# MCU_and_Power_Mgmt.net
KiCad netlist of a schematic drawn in Altium Designer
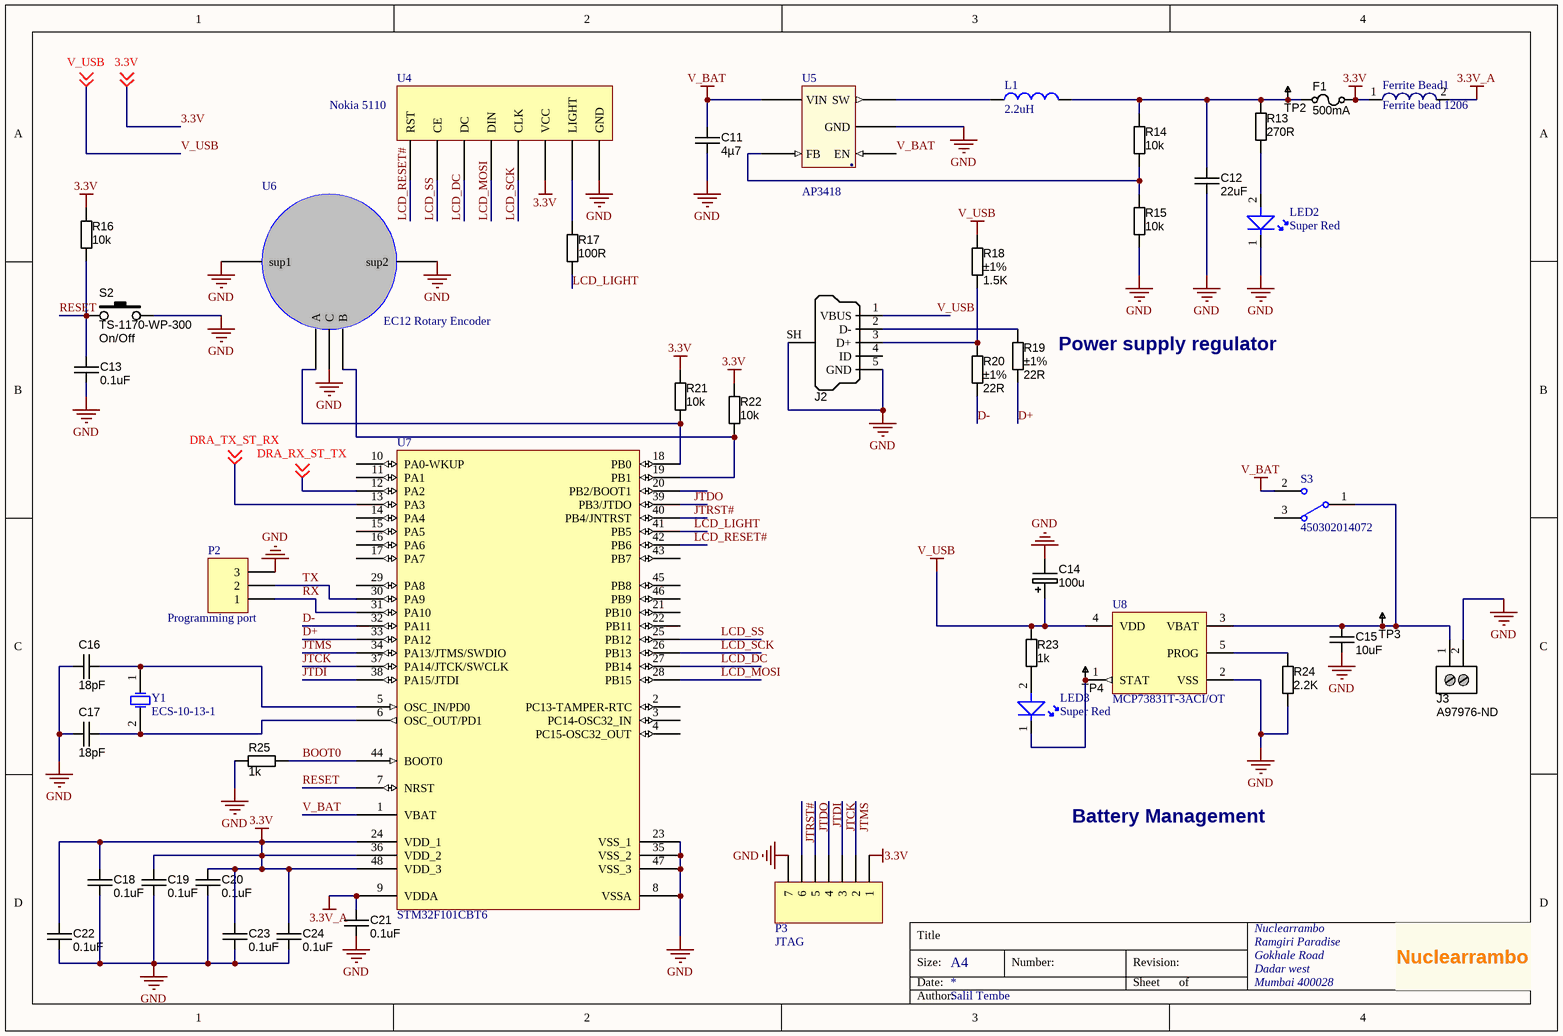
[diagram p0: MCU_and_Power_Mgmt.SchDoc]

(export (version "E")
  (design (tool "Eeschema 10.0.6"))
  (components
    (comp (ref "C11")
      (value "4µ7")
      (footprint "CAPMP3216X180N")
      (description "Capacitor SMD Cer 4.7uF 10% 16V X5R 0805")
      (fields (field (name "TOLERANCE") "±10%"))
      (libsource (lib "PBL - Capacitors") (part "CAPC_4u7_0805"))
    )
    (comp (ref "C12")
      (value "22uF")
      (footprint "CAPMP3216X180N")
      (description "Capacitor SMD Cer 4.7uF 10% 16V X5R 0805")
      (fields (field (name "TOLERANCE") "±10%"))
      (libsource (lib "PBL - Capacitors") (part "CAPC_4u7_0805"))
    )
    (comp (ref "C13")
      (value "0.1uF")
      (footprint "CAPC2012X135N")
      (description "Capacitor SMD Cer 10uF 10% 10V X5R 0805")
      (fields (field (name "TOLERANCE") "±10%"))
      (libsource (lib "PBL - Capacitors") (part "CAPC_10u_0805_10V"))
    )
    (comp (ref "C14")
      (value "100u")
      (footprint "CAPMP7343X310N")
      (description "Capacitor SMD Tant 330uF 20% 6V3 2917")
      (fields
        (field (name "TOLERANCE") "±20%")
        (field (name "MANUFACTURER PART NUMBER") "T520D337M006ATE015")
      )
      (libsource (lib "PBL - Capacitors") (part "CAPT_330u_2917_6V3"))
    )
    (comp (ref "C15")
      (value "10uF")
      (footprint "CAPMP3216X180N")
      (description "Capacitor SMD Cer 4.7uF 10% 16V X5R 0805")
      (fields (field (name "TOLERANCE") "±10%"))
      (libsource (lib "PBL - Capacitors") (part "CAPC_4u7_0805"))
    )
    (comp (ref "C16")
      (value "18pF")
      (footprint "CAPC2012X135N")
      (description "Capacitor SMD Cer 10uF 10% 10V X5R 0805")
      (fields (field (name "TOLERANCE") "±10%"))
      (libsource (lib "PBL - Capacitors") (part "CAPC_10u_0805_10V"))
    )
    (comp (ref "C17")
      (value "18pF")
      (footprint "CAPC2012X135N")
      (description "Capacitor SMD Cer 10uF 10% 10V X5R 0805")
      (fields (field (name "TOLERANCE") "±10%"))
      (libsource (lib "PBL - Capacitors") (part "CAPC_10u_0805_10V"))
    )
    (comp (ref "C18")
      (value "0.1uF")
      (footprint "CAPC2012X135N")
      (description "Capacitor SMD Cer 10uF 10% 10V X5R 0805")
      (fields (field (name "TOLERANCE") "±10%"))
      (libsource (lib "PBL - Capacitors") (part "CAPC_10u_0805_10V"))
    )
    (comp (ref "C19")
      (value "0.1uF")
      (footprint "CAPC2012X135N")
      (description "Capacitor SMD Cer 10uF 10% 10V X5R 0805")
      (fields (field (name "TOLERANCE") "±10%"))
      (libsource (lib "PBL - Capacitors") (part "CAPC_10u_0805_10V"))
    )
    (comp (ref "C20")
      (value "0.1uF")
      (footprint "CAPC2012X135N")
      (description "Capacitor SMD Cer 10uF 10% 10V X5R 0805")
      (fields (field (name "TOLERANCE") "±10%"))
      (libsource (lib "PBL - Capacitors") (part "CAPC_10u_0805_10V"))
    )
    (comp (ref "C21")
      (value "0.1uF")
      (footprint "CAPC2012X135N")
      (description "Capacitor SMD Cer 10uF 10% 10V X5R 0805")
      (fields (field (name "TOLERANCE") "±10%"))
      (libsource (lib "PBL - Capacitors") (part "CAPC_10u_0805_10V"))
    )
    (comp (ref "C22")
      (value "0.1uF")
      (footprint "CAPC2012X135N")
      (description "Capacitor SMD Cer 10uF 10% 10V X5R 0805")
      (fields (field (name "TOLERANCE") "±10%"))
      (libsource (lib "PBL - Capacitors") (part "CAPC_10u_0805_10V"))
    )
    (comp (ref "C23")
      (value "0.1uF")
      (footprint "CAPC2012X135N")
      (description "Capacitor SMD Cer 10uF 10% 10V X5R 0805")
      (fields (field (name "TOLERANCE") "±10%"))
      (libsource (lib "PBL - Capacitors") (part "CAPC_10u_0805_10V"))
    )
    (comp (ref "C24")
      (value "0.1uF")
      (footprint "CAPC2012X135N")
      (description "Capacitor SMD Cer 10uF 10% 10V X5R 0805")
      (fields (field (name "TOLERANCE") "±10%"))
      (libsource (lib "PBL - Capacitors") (part "CAPC_10u_0805_10V"))
    )
    (comp (ref "F1")
      (value "500mA")
      (footprint "RESC3216X70N")
      (description "Fuse 160mA 63VDC 1206 SMD")
      (fields (field (name "Comment") "Slow-blow"))
      (libsource (lib "PBL - Fuses and Protection") (part "FUSE_160mA_1206"))
    )
    (comp (ref "Ferrite Bead1")
      (value "Ferrite bead 1206")
      (footprint "SMD 1206")
      (description "SMD EMI Suppression Ferrite Beads WE-CBF, Z= 32 Ohm")
      (fields
        (field (name "PARTNO") "7427921")
        (field (name "MANUFACTURER") "Würth Elektronik eiSos GmbH")
        (field (name "CREATED BY") "Christin Zierenner")
      )
      (libsource (lib "WE-CBF_rev15a") (part "WE-CBF 1206, 7427921"))
    )
    (comp (ref "J2")
      (value "USB Micro Type B (recommended if hand soldering)")
      (footprint "USB_Micro-B_FCI_SMD")
      (description "Connector SMD-THD USB Micro Type B middle mount")
      (libsource (lib "PBL - Connectors") (part "USB_Micro_TypeB_FCI"))
    )
    (comp (ref "J3")
      (value "Stackable ScrewTerm")
      (footprint "2P_PCB_ScrewTerm_90S_3.81MM")
      (description "Terminal Block Screw Type THT 2-Position 3.81mm pitch")
      (fields (field (name "SUPPLIER PART NUMBER 1") "A97976-ND"))
      (libsource (lib "PBL - Connectors") (part "2P_ScrewTerm_90S_3.81MM"))
    )
    (comp (ref "L1")
      (value "2.2uH")
      (footprint "COILCRAFT_LPS4018")
      (description "IND 1800uH +/-20% 0.070A 31.5oh LPS4018")
      (fields (field (name "TOLERANCE") "+/-20%") (field (name "MANUFACTURER") "Coilcraft"))
      (libsource (lib "PassiveSMT") (part "Inductor1"))
    )
    (comp (ref "LED2")
      (value "Super Red")
      (footprint "Type 3mm")
      (description "THT LED round mono-color color lens, WL-TMRW, Super Red")
      (fields
        (field (name "PARTNO") "151031SS04000")
        (field (name "MANUFACTURER") "Würth Elektronik eiSos GmbH")
        (field (name "CREATED BY") "Christin Otto")
      )
      (libsource (lib "WL-TMRC_rev15a") (part "WL-TMRW, Type 3mm, 151031SS04000"))
    )
    (comp (ref "LED3")
      (value "Super Red")
      (footprint "Type 3mm")
      (description "THT LED round mono-color color lens, WL-TMRW, Super Red")
      (fields
        (field (name "PARTNO") "151031SS04000")
        (field (name "MANUFACTURER") "Würth Elektronik eiSos GmbH")
        (field (name "CREATED BY") "Christin Otto")
      )
      (libsource (lib "WL-TMRC_rev15a") (part "WL-TMRW, Type 3mm, 151031SS04000"))
    )
    (comp (ref "P2")
      (value "Programming port")
      (footprint "HDR1X3")
      (description "Header, 3-Pin")
      (fields (field (name "PUBLISHER") "Altium Limited"))
      (libsource (lib "Miscellaneous Connectors") (part "Header 3"))
    )
    (comp (ref "P3")
      (value "JTAG")
      (footprint "HDR1X7")
      (description "Header, 7-Pin")
      (fields (field (name "PUBLISHER") "Altium Limited"))
      (libsource (lib "Miscellaneous Connectors") (part "Header 7"))
    )
    (comp (ref "R13")
      (value "270R")
      (footprint "ERA-0805")
      (description "Resistor SMD chip 0.0 Ohm 0.125W 0805")
      (libsource (lib "PBL - Resistors") (part "RES_0R_0805"))
    )
    (comp (ref "R14")
      (value "10k")
      (footprint "ERA-0805")
      (description "Resistor SMD chip 0.0 Ohm 0.125W 0805")
      (libsource (lib "PBL - Resistors") (part "RES_0R_0805"))
    )
    (comp (ref "R15")
      (value "10k")
      (footprint "ERA-0805")
      (description "Resistor SMD chip 0.0 Ohm 0.125W 0805")
      (libsource (lib "PBL - Resistors") (part "RES_0R_0805"))
    )
    (comp (ref "R16")
      (value "10k")
      (footprint "ERA-0805")
      (description "Resistor SMD chip 0.0 Ohm 0.125W 0805")
      (libsource (lib "PBL - Resistors") (part "RES_0R_0805"))
    )
    (comp (ref "R17")
      (value "100R")
      (footprint "ERA-0805")
      (description "Resistor SMD chip 0.0 Ohm 0.125W 0805")
      (libsource (lib "PBL - Resistors") (part "RES_0R_0805"))
    )
    (comp (ref "R18")
      (value "1.5K")
      (footprint "RESC2012X70N")
      (description "Resistor SMD chip 100 Ohm 0.125W 1% 0805")
      (fields (field (name "TOLERANCE") "±1%"))
      (libsource (lib "PBL - Resistors") (part "RES_100R_0805_1%"))
    )
    (comp (ref "R19")
      (value "22R")
      (footprint "RESC2012X70N")
      (description "Resistor SMD chip 100 Ohm 0.125W 1% 0805")
      (fields (field (name "TOLERANCE") "±1%"))
      (libsource (lib "") (part "RES_100R_0805_1%_1"))
    )
    (comp (ref "R20")
      (value "22R")
      (footprint "RESC2012X70N")
      (description "Resistor SMD chip 100 Ohm 0.125W 1% 0805")
      (fields (field (name "TOLERANCE") "±1%"))
      (libsource (lib "PBL - Resistors") (part "RES_100R_0805_1%"))
    )
    (comp (ref "R21")
      (value "10k")
      (footprint "ERA-0805")
      (description "Resistor SMD chip 0.0 Ohm 0.125W 0805")
      (libsource (lib "PBL - Resistors") (part "RES_0R_0805"))
    )
    (comp (ref "R22")
      (value "10k")
      (footprint "ERA-0805")
      (description "Resistor SMD chip 0.0 Ohm 0.125W 0805")
      (libsource (lib "PBL - Resistors") (part "RES_0R_0805"))
    )
    (comp (ref "R23")
      (value "1k")
      (footprint "ERA-0805")
      (description "Resistor SMD chip 0.0 Ohm 0.125W 0805")
      (libsource (lib "") (part "RES_0R_0805_1"))
    )
    (comp (ref "R24")
      (value "2.2K")
      (footprint "ERA-0805")
      (description "Resistor SMD chip 0.0 Ohm 0.125W 0805")
      (libsource (lib "") (part "RES_0R_0805_1"))
    )
    (comp (ref "R25")
      (value "1k")
      (footprint "ERA-0805")
      (description "Resistor SMD chip 0.0 Ohm 0.125W 0805")
      (libsource (lib "") (part "RES_0R_0805_2"))
    )
    (comp (ref "S2")
      (value "SW_THT_PB_7.0mm")
      (footprint "TACT-SWITCH-TS1170")
      (description "Switch, tact, 7.0mm stem")
      (fields (field (name "MANUFACTURER PART NUMBER 1") "TS-1170-WP-300") (field (name "FUNCTION") "On/Off"))
      (libsource (lib "PBL - Switches") (part "SW_THT_PB_7.0mm"))
    )
    (comp (ref "S3")
      (value "450302014072")
      (footprint "450302014072")
      (description "WS-SLTU 10x2.5 mm THT right angled")
      (fields (field (name "MANUFACTURER") "Wurth Elektronik") (field (name "CREATED BY") "Baojun Chen"))
      (libsource (lib "WS-SLTU_rev15a") (part "WS-SLTU, 450302014072"))
    )
    (comp (ref "TP2")
      (value "TESTPOINT")
      (footprint "TP-R60")
      (description "SMD test pin")
      (libsource (lib "PBL - Test Points") (part "TESTPOINT"))
    )
    (comp (ref "TP3")
      (value "TESTPOINT")
      (footprint "TP-R60")
      (description "SMD test pin")
      (libsource (lib "PBL - Test Points") (part "TESTPOINT"))
    )
    (comp (ref "TP4")
      (value "TESTPOINT")
      (footprint "TP-R60")
      (description "SMD test pin")
      (libsource (lib "PBL - Test Points") (part "TESTPOINT"))
    )
    (comp (ref "U4")
      (value "Nokia 5110")
      (footprint "HDR1X8")
      (description "Nokia 5110 LCD module")
      (libsource (lib "nokia_and_random_stuff") (part "Nokia 5110"))
    )
    (comp (ref "U5")
      (value "AP3418")
      (footprint "SOT23-5")
      (description "DC/DC buck converter")
      (libsource (lib "AP3418") (part "AP3418"))
    )
    (comp (ref "U6")
      (value "EC12 Rotary Encoder")
      (footprint "EC12")
      (description "EC12 Rotary encoder")
      (libsource (lib "EC12_Rotary_encoder") (part "EC12 Rotary Encoder"))
    )
    (comp (ref "U7")
      (value "STM32F101CBT6")
      (footprint "LQFP48_N")
      (description "STM32 ARM-based 32-bit MCU with 128 Kbytes Flash, 48-pin LQFP, Industrial Temperature")
      (fields (field (name "PUBLISHER") "Altium Limited"))
      (libsource (lib "ST Microcontroller 32-Bit STM32") (part "STM32F101CBT6"))
    )
    (comp (ref "U8")
      (value "MCP73831T-3ACI/OT")
      (footprint "SOT-23-OT5_N")
      (fields (field (name "PUBLISHER") "Altium Limited"))
      (libsource (lib "Microchip Power Mgt Battery Management") (part "MCP73831T-3ACI/OT"))
    )
    (comp (ref "Y1")
      (value "ECS-10-13-1")
      (footprint "HC-49U")
      (description "Crystal Oscillator")
      (fields (field (name "PUBLISHER") "Altium Limited"))
      (libsource (lib "ECS Crystal Oscillator") (part "ECS-10-13-1"))
    )
  )
  (nets
    (net (code "1") (name "/BOOT0") (class "Default")
      (node (ref "R25") (pin "2") (pinfunction "2_2") (pintype "passive"))
      (node (ref "U7") (pin "44") (pinfunction "BOOT0_44") (pintype "input"))
    )
    (net (code "2") (name "/D+") (class "Default")
      (node (ref "R19") (pin "2") (pinfunction "2_2") (pintype "passive"))
      (node (ref "U7") (pin "33") (pinfunction "PA12_33") (pintype "bidirectional"))
    )
    (net (code "3") (name "/D-") (class "Default")
      (node (ref "R20") (pin "1") (pinfunction "1_1") (pintype "passive"))
      (node (ref "U7") (pin "32") (pinfunction "PA11_32") (pintype "bidirectional"))
    )
    (net (code "4") (name "/JTCK") (class "Default")
      (node (ref "P3") (pin "3") (pinfunction "3_3") (pintype "passive"))
      (node (ref "U7") (pin "37") (pinfunction "PA14/JTCK/SWCLK_37") (pintype "bidirectional"))
    )
    (net (code "5") (name "/JTDI") (class "Default")
      (node (ref "P3") (pin "4") (pinfunction "4_4") (pintype "passive"))
      (node (ref "U7") (pin "38") (pinfunction "PA15/JTDI_38") (pintype "bidirectional"))
    )
    (net (code "6") (name "/JTDO") (class "Default")
      (node (ref "P3") (pin "5") (pinfunction "5_5") (pintype "passive"))
      (node (ref "U7") (pin "39") (pinfunction "PB3/JTDO_39") (pintype "bidirectional"))
    )
    (net (code "7") (name "/JTMS") (class "Default")
      (node (ref "P3") (pin "2") (pinfunction "2_2") (pintype "passive"))
      (node (ref "U7") (pin "34") (pinfunction "PA13/JTMS/SWDIO_34") (pintype "bidirectional"))
    )
    (net (code "8") (name "/JTRST#") (class "Default")
      (node (ref "P3") (pin "6") (pinfunction "6_6") (pintype "passive"))
      (node (ref "U7") (pin "40") (pinfunction "PB4/JNTRST_40") (pintype "bidirectional"))
    )
    (net (code "9") (name "/LCD_DC") (class "Default")
      (node (ref "U4") (pin "6") (pinfunction "DC_6") (pintype "passive"))
      (node (ref "U7") (pin "27") (pinfunction "PB14_27") (pintype "bidirectional"))
    )
    (net (code "10") (name "/LCD_LIGHT") (class "Default")
      (node (ref "R17") (pin "2") (pinfunction "2_2") (pintype "passive"))
      (node (ref "U7") (pin "41") (pinfunction "PB5_41") (pintype "bidirectional"))
    )
    (net (code "11") (name "/LCD_MOSI") (class "Default")
      (node (ref "U4") (pin "5") (pinfunction "DIN_5") (pintype "passive"))
      (node (ref "U7") (pin "28") (pinfunction "PB15_28") (pintype "bidirectional"))
    )
    (net (code "12") (name "/LCD_RESET#") (class "Default")
      (node (ref "U4") (pin "8") (pinfunction "RST_8") (pintype "passive"))
      (node (ref "U7") (pin "42") (pinfunction "PB6_42") (pintype "bidirectional"))
    )
    (net (code "13") (name "/LCD_SCK") (class "Default")
      (node (ref "U4") (pin "4") (pinfunction "CLK_4") (pintype "passive"))
      (node (ref "U7") (pin "26") (pinfunction "PB13_26") (pintype "bidirectional"))
    )
    (net (code "14") (name "/LCD_SS") (class "Default")
      (node (ref "U4") (pin "7") (pinfunction "CE_7") (pintype "passive"))
      (node (ref "U7") (pin "25") (pinfunction "PB12_25") (pintype "bidirectional"))
    )
    (net (code "15") (name "/RESET") (class "Default")
      (node (ref "C13") (pin "2") (pintype "passive"))
      (node (ref "R16") (pin "2") (pinfunction "2_2") (pintype "passive"))
      (node (ref "S2") (pin "1") (pintype "passive"))
      (node (ref "U7") (pin "7") (pinfunction "NRST_7") (pintype "bidirectional"))
    )
    (net (code "16") (name "/RX") (class "Default")
      (node (ref "P2") (pin "1") (pinfunction "1_1") (pintype "passive"))
      (node (ref "U7") (pin "31") (pinfunction "PA10_31") (pintype "bidirectional"))
    )
    (net (code "17") (name "/TX") (class "Default")
      (node (ref "P2") (pin "2") (pinfunction "2_2") (pintype "passive"))
      (node (ref "U7") (pin "30") (pinfunction "PA9_30") (pintype "bidirectional"))
    )
    (net (code "18") (name "3.3V") (class "Default")
      (node (ref "C18") (pin "2") (pintype "passive"))
      (node (ref "C19") (pin "2") (pintype "passive"))
      (node (ref "C20") (pin "2") (pintype "passive"))
      (node (ref "C22") (pin "2") (pintype "passive"))
      (node (ref "C23") (pin "2") (pintype "passive"))
      (node (ref "C24") (pin "2") (pintype "passive"))
      (node (ref "F1") (pin "2") (pinfunction "2_2") (pintype "passive"))
      (node (ref "Ferrite Bead1") (pin "1") (pinfunction "1_1") (pintype "passive"))
      (node (ref "P3") (pin "1") (pinfunction "1_1") (pintype "passive"))
      (node (ref "R16") (pin "1") (pinfunction "1_1") (pintype "passive"))
      (node (ref "R21") (pin "1") (pinfunction "1_1") (pintype "passive"))
      (node (ref "R22") (pin "1") (pinfunction "1_1") (pintype "passive"))
      (node (ref "U4") (pin "3") (pinfunction "VCC_3") (pintype "passive"))
      (node (ref "U7") (pin "24") (pinfunction "VDD_1_24") (pintype "power_in"))
      (node (ref "U7") (pin "36") (pinfunction "VDD_2_36") (pintype "power_in"))
      (node (ref "U7") (pin "48") (pinfunction "VDD_3_48") (pintype "power_in"))
    )
    (net (code "19") (name "3.3V_A") (class "Default")
      (node (ref "C21") (pin "2") (pintype "passive"))
      (node (ref "Ferrite Bead1") (pin "2") (pinfunction "2_2") (pintype "passive"))
      (node (ref "U7") (pin "9") (pinfunction "VDDA_9") (pintype "power_in"))
    )
    (net (code "20") (name "DRA_RX_ST_TX") (class "Default")
      (node (ref "U7") (pin "12") (pinfunction "PA2_12") (pintype "bidirectional"))
    )
    (net (code "21") (name "DRA_TX_ST_RX") (class "Default")
      (node (ref "U7") (pin "13") (pinfunction "PA3_13") (pintype "bidirectional"))
    )
    (net (code "22") (name "GND") (class "Default")
      (node (ref "C11") (pin "2") (pintype "passive"))
      (node (ref "C12") (pin "2") (pintype "passive"))
      (node (ref "C13") (pin "1") (pintype "passive"))
      (node (ref "C14") (pin "2") (pintype "passive"))
      (node (ref "C15") (pin "2") (pintype "passive"))
      (node (ref "C16") (pin "1") (pintype "passive"))
      (node (ref "C17") (pin "1") (pintype "passive"))
      (node (ref "C18") (pin "1") (pintype "passive"))
      (node (ref "C19") (pin "1") (pintype "passive"))
      (node (ref "C20") (pin "1") (pintype "passive"))
      (node (ref "C21") (pin "1") (pintype "passive"))
      (node (ref "C22") (pin "1") (pintype "passive"))
      (node (ref "C23") (pin "1") (pintype "passive"))
      (node (ref "C24") (pin "1") (pintype "passive"))
      (node (ref "J2") (pin "5") (pinfunction "GND_5") (pintype "passive"))
      (node (ref "J2") (pin "SH") (pinfunction "Shell_SH") (pintype "passive"))
      (node (ref "J3") (pin "2") (pinfunction "2_2") (pintype "passive"))
      (node (ref "LED2") (pin "1") (pinfunction "K_1") (pintype "passive"))
      (node (ref "P2") (pin "3") (pinfunction "3_3") (pintype "passive"))
      (node (ref "P3") (pin "7") (pinfunction "7_7") (pintype "passive"))
      (node (ref "R15") (pin "2") (pinfunction "2_2") (pintype "passive"))
      (node (ref "R24") (pin "1") (pinfunction "1_1") (pintype "passive"))
      (node (ref "R25") (pin "1") (pinfunction "1_1") (pintype "passive"))
      (node (ref "S2") (pin "2") (pintype "passive"))
      (node (ref "U4") (pin "1") (pinfunction "GND_1") (pintype "passive"))
      (node (ref "U5") (pin "2") (pinfunction "GND_2") (pintype "power_in"))
      (node (ref "U6") (pin "C") (pinfunction "C_C") (pintype "passive"))
      (node (ref "U6") (pin "sup1") (pinfunction "sup1_sup1") (pintype "passive"))
      (node (ref "U6") (pin "sup2") (pinfunction "sup2_sup2") (pintype "passive"))
      (node (ref "U7") (pin "23") (pinfunction "VSS_1_23") (pintype "power_in"))
      (node (ref "U7") (pin "35") (pinfunction "VSS_2_35") (pintype "power_in"))
      (node (ref "U7") (pin "47") (pinfunction "VSS_3_47") (pintype "power_in"))
      (node (ref "U7") (pin "8") (pinfunction "VSSA_8") (pintype "power_in"))
      (node (ref "U8") (pin "2") (pinfunction "VSS_2") (pintype "power_in"))
    )
    (net (code "23") (name "Net-(C12-Pad1)") (class "Default")
      (node (ref "C12") (pin "1") (pintype "passive"))
      (node (ref "F1") (pin "1") (pinfunction "1_1") (pintype "passive"))
      (node (ref "L1") (pin "2") (pinfunction "2_2") (pintype "passive"))
      (node (ref "R13") (pin "1") (pinfunction "1_1") (pintype "passive"))
      (node (ref "R14") (pin "1") (pinfunction "1_1") (pintype "passive"))
      (node (ref "TP2") (pin "1") (pintype "passive"))
    )
    (net (code "24") (name "Net-(J2-D+)") (class "Default")
      (node (ref "J2") (pin "3") (pinfunction "D+_3") (pintype "passive"))
      (node (ref "R18") (pin "1") (pinfunction "1_1") (pintype "passive"))
      (node (ref "R20") (pin "2") (pinfunction "2_2") (pintype "passive"))
    )
    (net (code "25") (name "Net-(J2-D-)") (class "Default")
      (node (ref "J2") (pin "2") (pinfunction "D-_2") (pintype "passive"))
      (node (ref "R19") (pin "1") (pinfunction "1_1") (pintype "passive"))
    )
    (net (code "26") (name "Net-(LED2-A)") (class "Default")
      (node (ref "LED2") (pin "2") (pinfunction "A_2") (pintype "passive"))
      (node (ref "R13") (pin "2") (pinfunction "2_2") (pintype "passive"))
    )
    (net (code "27") (name "Net-(LED3-A)") (class "Default")
      (node (ref "LED3") (pin "2") (pinfunction "A_2") (pintype "passive"))
      (node (ref "R23") (pin "1") (pinfunction "1_1") (pintype "passive"))
    )
    (net (code "28") (name "Net-(LED3-K)") (class "Default")
      (node (ref "LED3") (pin "1") (pinfunction "K_1") (pintype "passive"))
      (node (ref "TP4") (pin "1") (pintype "passive"))
      (node (ref "U8") (pin "1") (pinfunction "STAT_1") (pintype "output"))
    )
    (net (code "29") (name "Net-(U4-LIGHT)") (class "Default")
      (node (ref "R17") (pin "1") (pinfunction "1_1") (pintype "passive"))
      (node (ref "U4") (pin "2") (pinfunction "LIGHT_2") (pintype "passive"))
    )
    (net (code "30") (name "Net-(U5-FB)") (class "Default")
      (node (ref "R14") (pin "2") (pinfunction "2_2") (pintype "passive"))
      (node (ref "R15") (pin "1") (pinfunction "1_1") (pintype "passive"))
      (node (ref "U5") (pin "5") (pinfunction "FB_5") (pintype "input"))
    )
    (net (code "31") (name "Net-(U5-SW)") (class "Default")
      (node (ref "L1") (pin "1") (pinfunction "1_1") (pintype "passive"))
      (node (ref "U5") (pin "3") (pinfunction "SW_3") (pintype "output"))
    )
    (net (code "32") (name "Net-(U7-OSC_IN{slash}PD0)") (class "Default")
      (node (ref "C16") (pin "2") (pintype "passive"))
      (node (ref "U7") (pin "5") (pinfunction "OSC_IN/PD0_5") (pintype "input"))
      (node (ref "Y1") (pin "1") (pinfunction "OSC1_1") (pintype "passive"))
    )
    (net (code "33") (name "Net-(U7-OSC_OUT{slash}PD1)") (class "Default")
      (node (ref "C17") (pin "2") (pintype "passive"))
      (node (ref "U7") (pin "6") (pinfunction "OSC_OUT/PD1_6") (pintype "output"))
      (node (ref "Y1") (pin "2") (pinfunction "OSC2_2") (pintype "passive"))
    )
    (net (code "34") (name "Net-(U7-PB0)") (class "Default")
      (node (ref "R21") (pin "2") (pinfunction "2_2") (pintype "passive"))
      (node (ref "U6") (pin "A") (pinfunction "A_A") (pintype "passive"))
      (node (ref "U7") (pin "18") (pinfunction "PB0_18") (pintype "bidirectional"))
    )
    (net (code "35") (name "Net-(U7-PB1)") (class "Default")
      (node (ref "R22") (pin "2") (pinfunction "2_2") (pintype "passive"))
      (node (ref "U6") (pin "B") (pinfunction "B_B") (pintype "passive"))
      (node (ref "U7") (pin "19") (pinfunction "PB1_19") (pintype "bidirectional"))
    )
    (net (code "36") (name "Net-(U8-PROG)") (class "Default")
      (node (ref "R24") (pin "2") (pinfunction "2_2") (pintype "passive"))
      (node (ref "U8") (pin "5") (pinfunction "PROG_5") (pintype "passive"))
    )
    (net (code "37") (name "Net-(U8-VBAT)") (class "Default")
      (node (ref "C15") (pin "1") (pintype "passive"))
      (node (ref "J3") (pin "1") (pinfunction "1_1") (pintype "passive"))
      (node (ref "S3") (pin "1") (pinfunction "1_1") (pintype "passive"))
      (node (ref "TP3") (pin "1") (pintype "passive"))
      (node (ref "U8") (pin "3") (pinfunction "VBAT_3") (pintype "power_in"))
    )
    (net (code "38") (name "V_BAT") (class "Default")
      (node (ref "C11") (pin "1") (pintype "passive"))
      (node (ref "S3") (pin "2") (pinfunction "2_2") (pintype "passive"))
      (node (ref "U5") (pin "1") (pinfunction "EN_1") (pintype "input"))
      (node (ref "U5") (pin "4") (pinfunction "VIN_4") (pintype "power_in"))
      (node (ref "U7") (pin "1") (pinfunction "VBAT_1") (pintype "power_in"))
    )
    (net (code "39") (name "V_USB") (class "Default")
      (node (ref "C14") (pin "1") (pintype "passive"))
      (node (ref "J2") (pin "1") (pinfunction "VBUS_1") (pintype "passive"))
      (node (ref "R18") (pin "2") (pinfunction "2_2") (pintype "passive"))
      (node (ref "R23") (pin "2") (pinfunction "2_2") (pintype "passive"))
      (node (ref "U8") (pin "4") (pinfunction "VDD_4") (pintype "power_in"))
    )
    (net (code "40") (name "unconnected-(J2-ID-Pad4)") (class "Default")
      (node (ref "J2") (pin "4") (pinfunction "ID_4") (pintype "passive"))
    )
    (net (code "41") (name "unconnected-(S3-Pad3)") (class "Default")
      (node (ref "S3") (pin "3") (pinfunction "3_3") (pintype "passive"))
    )
    (net (code "42") (name "unconnected-(U7-PA0-WKUP-Pad10)") (class "Default")
      (node (ref "U7") (pin "10") (pinfunction "PA0-WKUP_10") (pintype "bidirectional"))
    )
    (net (code "43") (name "unconnected-(U7-PA1-Pad11)") (class "Default")
      (node (ref "U7") (pin "11") (pinfunction "PA1_11") (pintype "bidirectional"))
    )
    (net (code "44") (name "unconnected-(U7-PA4-Pad14)") (class "Default")
      (node (ref "U7") (pin "14") (pinfunction "PA4_14") (pintype "bidirectional"))
    )
    (net (code "45") (name "unconnected-(U7-PA5-Pad15)") (class "Default")
      (node (ref "U7") (pin "15") (pinfunction "PA5_15") (pintype "bidirectional"))
    )
    (net (code "46") (name "unconnected-(U7-PA6-Pad16)") (class "Default")
      (node (ref "U7") (pin "16") (pinfunction "PA6_16") (pintype "bidirectional"))
    )
    (net (code "47") (name "unconnected-(U7-PA7-Pad17)") (class "Default")
      (node (ref "U7") (pin "17") (pinfunction "PA7_17") (pintype "bidirectional"))
    )
    (net (code "48") (name "unconnected-(U7-PA8-Pad29)") (class "Default")
      (node (ref "U7") (pin "29") (pinfunction "PA8_29") (pintype "bidirectional"))
    )
    (net (code "49") (name "unconnected-(U7-PB2{slash}BOOT1-Pad20)") (class "Default")
      (node (ref "U7") (pin "20") (pinfunction "PB2/BOOT1_20") (pintype "bidirectional"))
    )
    (net (code "50") (name "unconnected-(U7-PB7-Pad43)") (class "Default")
      (node (ref "U7") (pin "43") (pinfunction "PB7_43") (pintype "bidirectional"))
    )
    (net (code "51") (name "unconnected-(U7-PB8-Pad45)") (class "Default")
      (node (ref "U7") (pin "45") (pinfunction "PB8_45") (pintype "bidirectional"))
    )
    (net (code "52") (name "unconnected-(U7-PB9-Pad46)") (class "Default")
      (node (ref "U7") (pin "46") (pinfunction "PB9_46") (pintype "bidirectional"))
    )
    (net (code "53") (name "unconnected-(U7-PB10-Pad21)") (class "Default")
      (node (ref "U7") (pin "21") (pinfunction "PB10_21") (pintype "bidirectional"))
    )
    (net (code "54") (name "unconnected-(U7-PB11-Pad22)") (class "Default")
      (node (ref "U7") (pin "22") (pinfunction "PB11_22") (pintype "bidirectional"))
    )
    (net (code "55") (name "unconnected-(U7-PC13-TAMPER-RTC-Pad2)") (class "Default")
      (node (ref "U7") (pin "2") (pinfunction "PC13-TAMPER-RTC_2") (pintype "bidirectional"))
    )
    (net (code "56") (name "unconnected-(U7-PC14-OSC32_IN-Pad3)") (class "Default")
      (node (ref "U7") (pin "3") (pinfunction "PC14-OSC32_IN_3") (pintype "bidirectional"))
    )
    (net (code "57") (name "unconnected-(U7-PC15-OSC32_OUT-Pad4)") (class "Default")
      (node (ref "U7") (pin "4") (pinfunction "PC15-OSC32_OUT_4") (pintype "bidirectional"))
    )
  )
)
